# encoder-breakout.net
KiCad netlist of a schematic drawn in EAGLE
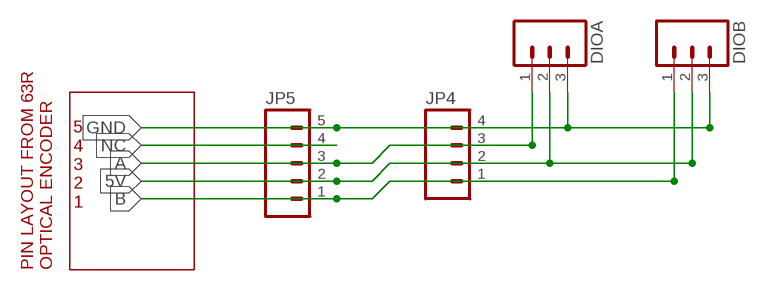
[diagram p0: schematic, sheet 1]

(export (version "E")
  (design (tool "Eeschema 10.0.6"))
  (components
    (comp (ref "DIOA")
      (value "M03LOCK")
      (footprint "eagle-import:1X03_LOCK")
      (libsource (lib "eagle-import") (part "M03LOCK"))
    )
    (comp (ref "DIOB")
      (value "M03LOCK")
      (footprint "eagle-import:1X03_LOCK")
      (libsource (lib "eagle-import") (part "M03LOCK"))
    )
    (comp (ref "JP4")
      (value "M04LOCK")
      (footprint "eagle-import:1X04_LOCK")
      (libsource (lib "eagle-import") (part "M04LOCK"))
    )
    (comp (ref "JP5")
      (value "M05LOCK")
      (footprint "eagle-import:1X05_LOCK")
      (libsource (lib "eagle-import") (part "M05LOCK"))
    )
  )
  (nets
    (net (code "1") (name "5V") (class "Default")
      (node (ref "DIOA") (pin "2") (pinfunction "2_2") (pintype "passive"))
      (node (ref "DIOB") (pin "2") (pinfunction "2_2") (pintype "passive"))
      (node (ref "JP4") (pin "2") (pinfunction "2_2") (pintype "passive"))
      (node (ref "JP5") (pin "2") (pinfunction "2_2") (pintype "passive"))
    )
    (net (code "2") (name "A") (class "Default")
      (node (ref "DIOA") (pin "1") (pinfunction "1_1") (pintype "passive"))
      (node (ref "JP4") (pin "3") (pinfunction "3_3") (pintype "passive"))
      (node (ref "JP5") (pin "3") (pinfunction "3_3") (pintype "passive"))
    )
    (net (code "3") (name "B") (class "Default")
      (node (ref "DIOB") (pin "1") (pinfunction "1_1") (pintype "passive"))
      (node (ref "JP4") (pin "1") (pinfunction "1_1") (pintype "passive"))
      (node (ref "JP5") (pin "1") (pinfunction "1_1") (pintype "passive"))
    )
    (net (code "4") (name "GND") (class "Default")
      (node (ref "DIOA") (pin "3") (pinfunction "3_3") (pintype "passive"))
      (node (ref "DIOB") (pin "3") (pinfunction "3_3") (pintype "passive"))
      (node (ref "JP4") (pin "4") (pinfunction "4_4") (pintype "passive"))
      (node (ref "JP5") (pin "5") (pinfunction "5_5") (pintype "passive"))
    )
    (net (code "5") (name "NC") (class "Default")
      (node (ref "JP5") (pin "4") (pinfunction "4_4") (pintype "passive"))
    )
  )
)
